# Sheet_2.net
KiCad netlist of a schematic drawn in EasyEDA
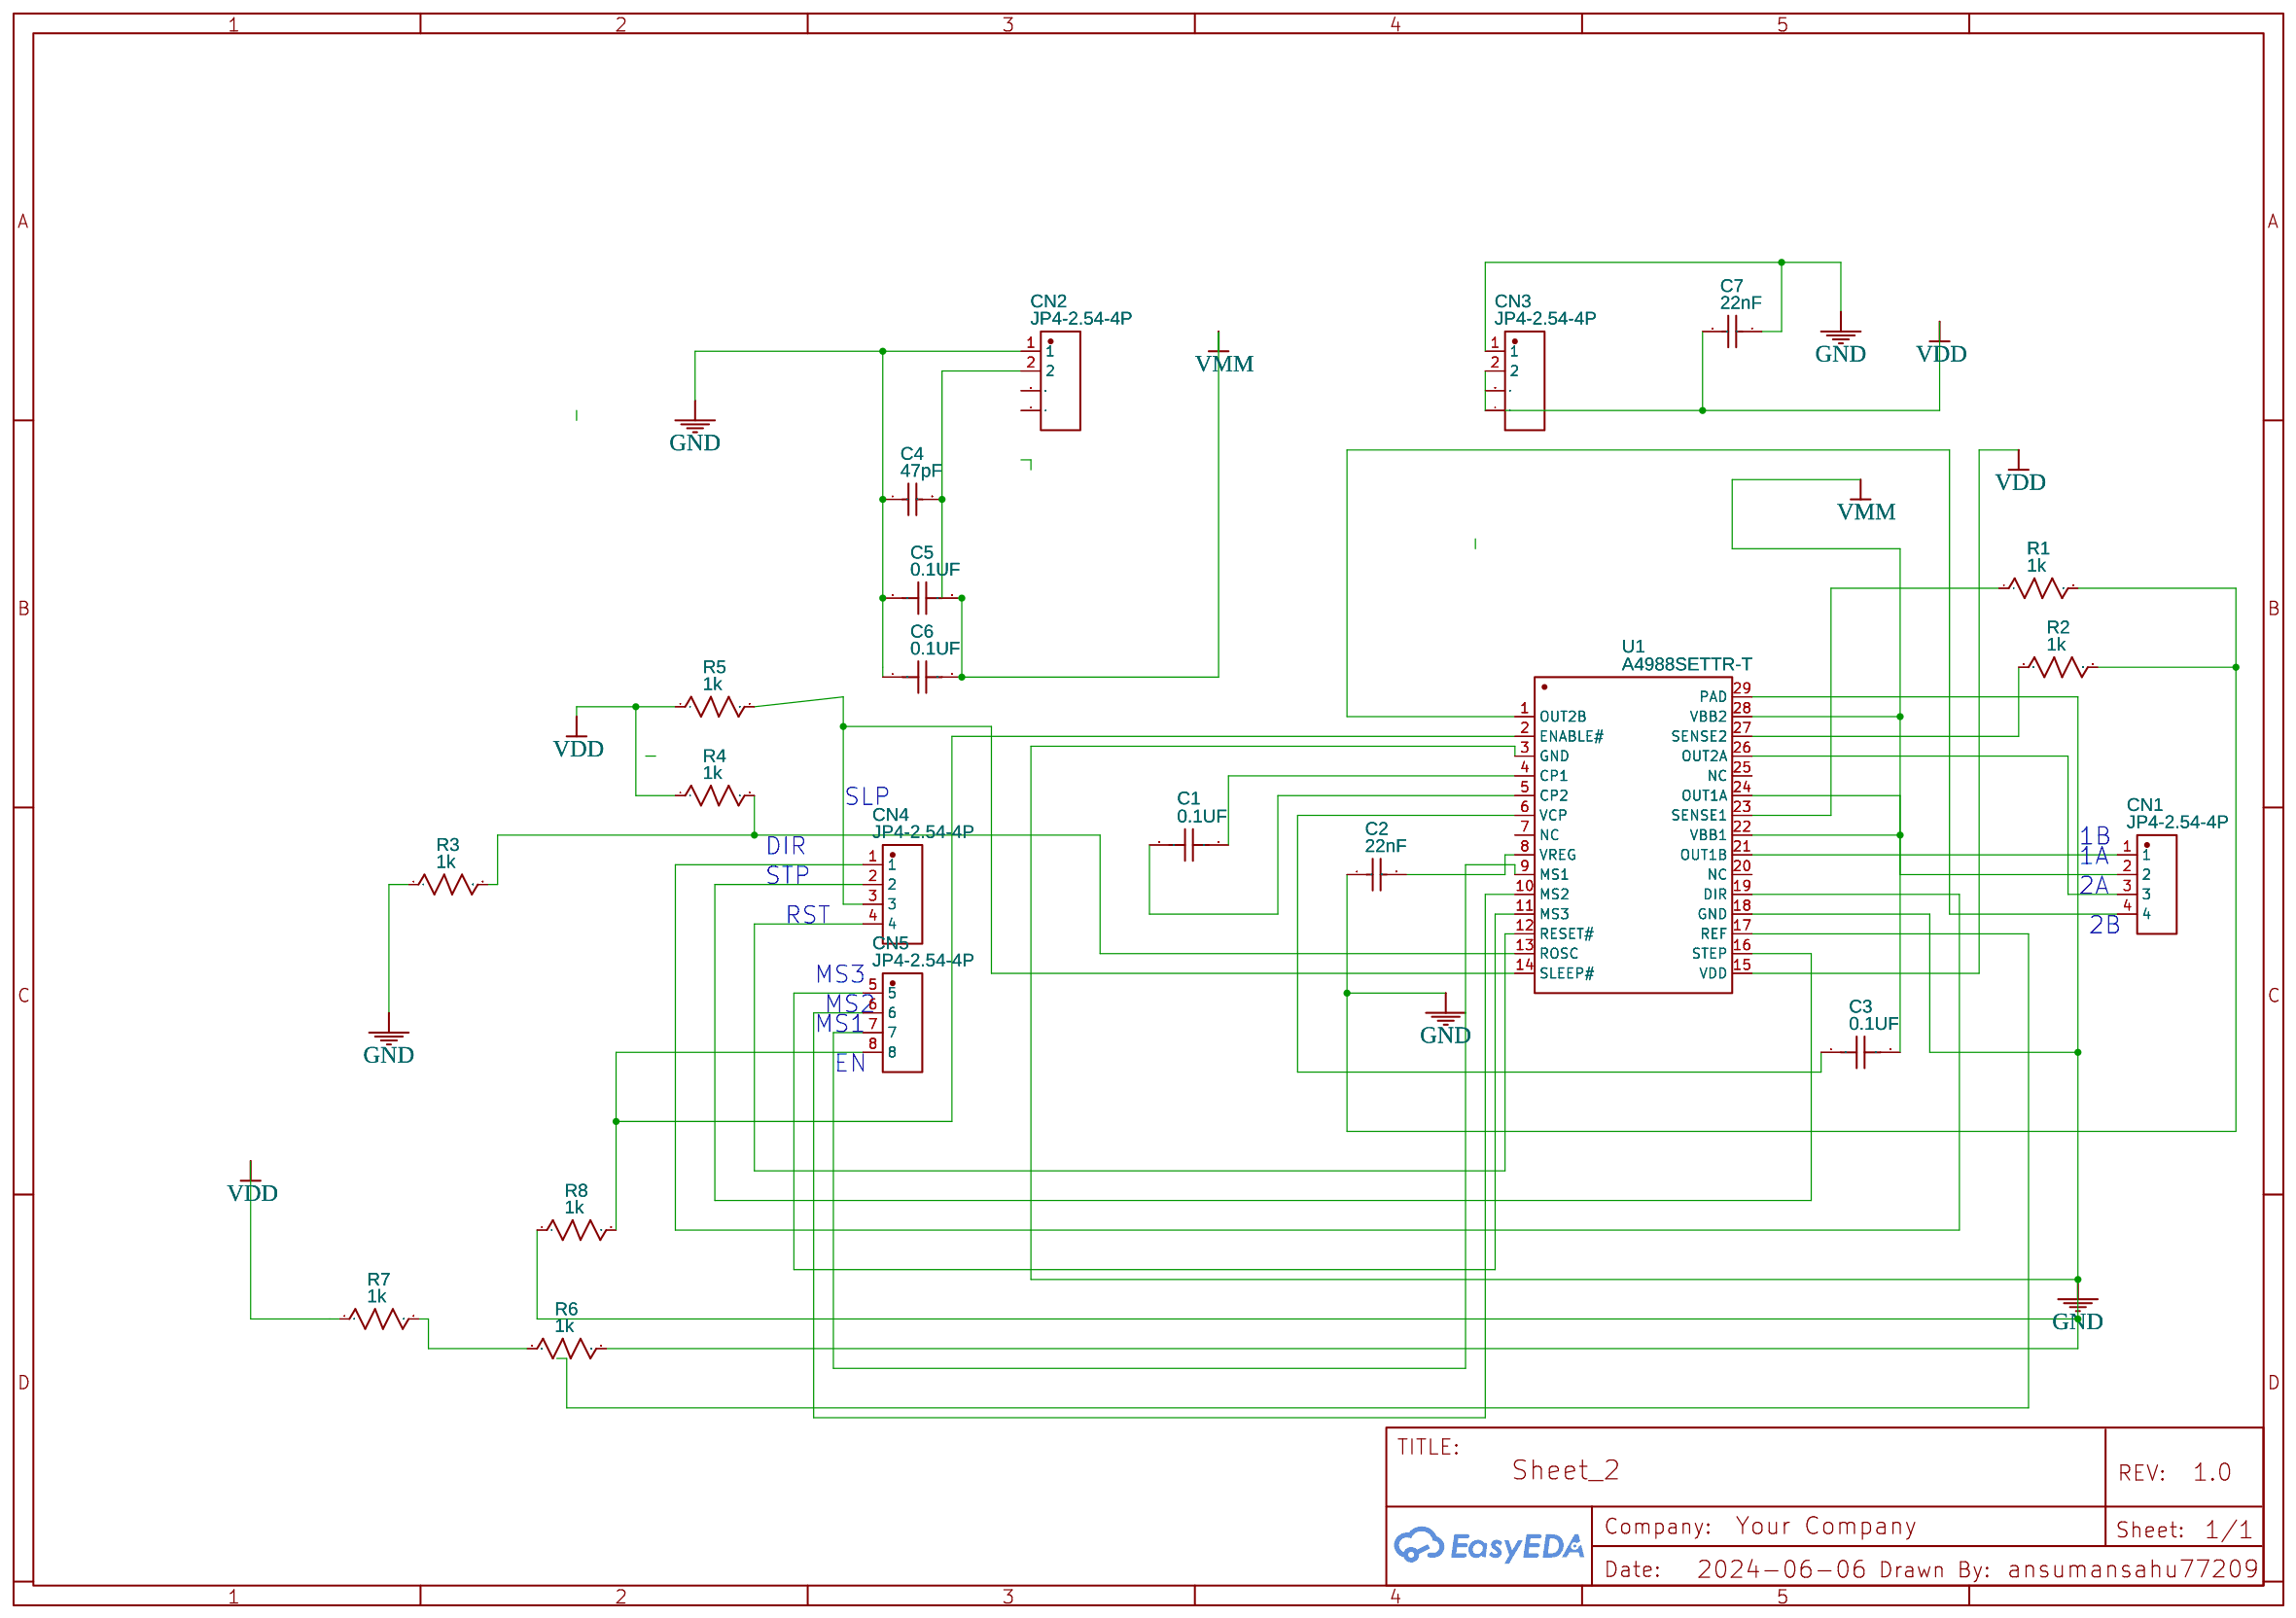
[diagram p0: schematic sheet]

(export (version "E")
  (design (tool "Eeschema 10.0.6"))
  (components
    (comp (ref "C1")
      (value "0.1UF")
      (fields
        (field (name "Manufacturer Part") "250V 0.1UF 5% CBBCapacitor")
        (field (name "Manufacturer") "ReliaPro")
      )
      (libsource (lib "") (part "250V 0.1UF 5% CBBCapacitor"))
    )
    (comp (ref "C2")
      (value "22nF")
      (fields
        (field (name "Manufacturer Part") "Calibration capacitor22NF（223） 100V 5%")
        (field (name "Manufacturer") "ReliaPro")
      )
      (libsource (lib "") (part "Calibration capacitor22NF（223） 100V 5%"))
    )
    (comp (ref "C3")
      (value "0.1UF")
      (fields
        (field (name "Manufacturer Part") "250V 0.1UF 5% CBBCapacitor")
        (field (name "Manufacturer") "ReliaPro")
      )
      (libsource (lib "") (part "250V 0.1UF 5% CBBCapacitor"))
    )
    (comp (ref "C4")
      (value "47pF")
      (fields (field (name "Manufacturer Part") "瓷片电容47PF 3KV"))
      (libsource (lib "") (part "Ceramic capacitors47PF 3KV"))
    )
    (comp (ref "C5")
      (value "0.1UF")
      (fields
        (field (name "Manufacturer Part") "250V 0.1UF 5% CBBCapacitor")
        (field (name "Manufacturer") "ReliaPro")
      )
      (libsource (lib "") (part "250V 0.1UF 5% CBBCapacitor"))
    )
    (comp (ref "C6")
      (value "0.1UF")
      (fields
        (field (name "Manufacturer Part") "250V 0.1UF 5% CBBCapacitor")
        (field (name "Manufacturer") "ReliaPro")
      )
      (libsource (lib "") (part "250V 0.1UF 5% CBBCapacitor"))
    )
    (comp (ref "C7")
      (value "22nF")
      (fields
        (field (name "Manufacturer Part") "Calibration capacitor22NF（223） 100V 5%")
        (field (name "Manufacturer") "ReliaPro")
      )
      (libsource (lib "") (part "Calibration capacitor22NF（223） 100V 5%"))
    )
    (comp (ref "CN1") (value "JP4-2.54-4P") (libsource (lib "") (part "JP4-2.54-4P")))
    (comp (ref "CN2") (value "JP4-2.54-4P") (libsource (lib "") (part "JP4-2.54-4P")))
    (comp (ref "CN3") (value "JP4-2.54-4P") (libsource (lib "") (part "JP4-2.54-4P")))
    (comp (ref "CN4") (value "JP4-2.54-4P") (libsource (lib "") (part "JP4-2.54-4P")))
    (comp (ref "CN5") (value "JP4-2.54-4P") (libsource (lib "") (part "JP4-2.54-4P_1")))
    (comp (ref "R1") (value "1k") (libsource (lib "") (part "R_0603_US")))
    (comp (ref "R2") (value "1k") (libsource (lib "") (part "R_0603_US")))
    (comp (ref "R3") (value "1k") (libsource (lib "") (part "R_0603_US")))
    (comp (ref "R4") (value "1k") (libsource (lib "") (part "R_0603_US")))
    (comp (ref "R5") (value "1k") (libsource (lib "") (part "R_0603_US")))
    (comp (ref "R6") (value "1k") (libsource (lib "") (part "R_0603_US")))
    (comp (ref "R7") (value "1k") (libsource (lib "") (part "R_0603_US")))
    (comp (ref "R8") (value "1k") (libsource (lib "") (part "R_0603_US")))
    (comp (ref "U1")
      (value "A4988SETTR-T")
      (fields (field (name "Manufacturer") "ALLEGRO(美国埃戈罗)"))
      (libsource (lib "") (part "A4988SETTR-T"))
    )
  )
  (nets
    (net (code "1") (name "GND") (class "Default")
      (node (ref "C2") (pin "1") (pinfunction "1_1") (pintype "input"))
      (node (ref "C4") (pin "1") (pinfunction "1_1") (pintype "input"))
      (node (ref "C5") (pin "1") (pinfunction "1_1") (pintype "unspecified"))
      (node (ref "C6") (pin "1") (pinfunction "1_1") (pintype "unspecified"))
      (node (ref "C7") (pin "2") (pinfunction "2_2") (pintype "input"))
      (node (ref "CN2") (pin "1") (pinfunction "1_1") (pintype "unspecified"))
      (node (ref "CN3") (pin "1") (pinfunction "1_1") (pintype "unspecified"))
      (node (ref "R1") (pin "2") (pinfunction "2_2") (pintype "unspecified"))
      (node (ref "R2") (pin "2") (pinfunction "2_2") (pintype "unspecified"))
      (node (ref "R3") (pin "1") (pinfunction "1_1") (pintype "unspecified"))
      (node (ref "R6") (pin "2") (pinfunction "2_2") (pintype "unspecified"))
      (node (ref "R8") (pin "1") (pinfunction "1_1") (pintype "unspecified"))
      (node (ref "U1") (pin "18") (pinfunction "GND_18") (pintype "unspecified"))
      (node (ref "U1") (pin "29") (pinfunction "PAD_29") (pintype "unspecified"))
      (node (ref "U1") (pin "3") (pinfunction "GND_3") (pintype "unspecified"))
    )
    (net (code "2") (name "Net-(R6-Pad1)") (class "Default")
      (node (ref "R6") (pin "1") (pinfunction "1_1") (pintype "unspecified"))
      (node (ref "R7") (pin "2") (pinfunction "2_2") (pintype "unspecified"))
    )
    (net (code "3") (name "Net-(U1-CP1)") (class "Default")
      (node (ref "C1") (pin "2") (pinfunction "2_2") (pintype "unspecified"))
      (node (ref "U1") (pin "4") (pinfunction "CP1_4") (pintype "unspecified"))
    )
    (net (code "4") (name "Net-(U1-CP2)") (class "Default")
      (node (ref "C1") (pin "1") (pinfunction "1_1") (pintype "unspecified"))
      (node (ref "U1") (pin "5") (pinfunction "CP2_5") (pintype "unspecified"))
    )
    (net (code "5") (name "Net-(U1-DIR)") (class "Default")
      (node (ref "CN4") (pin "1") (pinfunction "1_1") (pintype "unspecified"))
      (node (ref "U1") (pin "19") (pinfunction "DIR_19") (pintype "unspecified"))
    )
    (net (code "6") (name "Net-(U1-ENABLE#)") (class "Default")
      (node (ref "CN5") (pin "8") (pinfunction "8_8") (pintype "unspecified"))
      (node (ref "R8") (pin "2") (pinfunction "2_2") (pintype "unspecified"))
      (node (ref "U1") (pin "2") (pinfunction "ENABLE#_2") (pintype "unspecified"))
    )
    (net (code "7") (name "Net-(U1-MS1)") (class "Default")
      (node (ref "CN5") (pin "7") (pinfunction "7_7") (pintype "unspecified"))
      (node (ref "U1") (pin "9") (pinfunction "MS1_9") (pintype "unspecified"))
    )
    (net (code "8") (name "Net-(U1-MS2)") (class "Default")
      (node (ref "CN5") (pin "6") (pinfunction "6_6") (pintype "unspecified"))
      (node (ref "U1") (pin "10") (pinfunction "MS2_10") (pintype "unspecified"))
    )
    (net (code "9") (name "Net-(U1-MS3)") (class "Default")
      (node (ref "CN5") (pin "5") (pinfunction "5_5") (pintype "unspecified"))
      (node (ref "U1") (pin "11") (pinfunction "MS3_11") (pintype "unspecified"))
    )
    (net (code "10") (name "Net-(U1-OUT1B)") (class "Default")
      (node (ref "CN1") (pin "1") (pinfunction "1_1") (pintype "unspecified"))
      (node (ref "U1") (pin "21") (pinfunction "OUT1B_21") (pintype "unspecified"))
    )
    (net (code "11") (name "Net-(U1-OUT2A)") (class "Default")
      (node (ref "CN1") (pin "3") (pinfunction "3_3") (pintype "unspecified"))
      (node (ref "U1") (pin "26") (pinfunction "OUT2A_26") (pintype "unspecified"))
    )
    (net (code "12") (name "Net-(U1-OUT2B)") (class "Default")
      (node (ref "CN1") (pin "4") (pinfunction "4_4") (pintype "unspecified"))
      (node (ref "U1") (pin "1") (pinfunction "OUT2B_1") (pintype "unspecified"))
    )
    (net (code "13") (name "Net-(U1-RESET#)") (class "Default")
      (node (ref "CN4") (pin "4") (pinfunction "4_4") (pintype "unspecified"))
      (node (ref "U1") (pin "12") (pinfunction "RESET#_12") (pintype "unspecified"))
    )
    (net (code "14") (name "Net-(U1-ROSC)") (class "Default")
      (node (ref "R3") (pin "2") (pinfunction "2_2") (pintype "unspecified"))
      (node (ref "R4") (pin "2") (pinfunction "2_2") (pintype "unspecified"))
      (node (ref "U1") (pin "13") (pinfunction "ROSC_13") (pintype "unspecified"))
    )
    (net (code "15") (name "Net-(U1-SENSE1)") (class "Default")
      (node (ref "R1") (pin "1") (pinfunction "1_1") (pintype "unspecified"))
      (node (ref "U1") (pin "23") (pinfunction "SENSE1_23") (pintype "unspecified"))
    )
    (net (code "16") (name "Net-(U1-SENSE2)") (class "Default")
      (node (ref "R2") (pin "1") (pinfunction "1_1") (pintype "unspecified"))
      (node (ref "U1") (pin "27") (pinfunction "SENSE2_27") (pintype "unspecified"))
    )
    (net (code "17") (name "Net-(U1-SLEEP#)") (class "Default")
      (node (ref "CN4") (pin "3") (pinfunction "3_3") (pintype "unspecified"))
      (node (ref "R5") (pin "2") (pinfunction "2_2") (pintype "unspecified"))
      (node (ref "U1") (pin "14") (pinfunction "SLEEP#_14") (pintype "unspecified"))
    )
    (net (code "18") (name "Net-(U1-STEP)") (class "Default")
      (node (ref "CN4") (pin "2") (pinfunction "2_2") (pintype "unspecified"))
      (node (ref "U1") (pin "16") (pinfunction "STEP_16") (pintype "unspecified"))
    )
    (net (code "19") (name "Net-(U1-VCP)") (class "Default")
      (node (ref "C3") (pin "1") (pinfunction "1_1") (pintype "unspecified"))
      (node (ref "U1") (pin "6") (pinfunction "VCP_6") (pintype "unspecified"))
    )
    (net (code "20") (name "Net-(U1-VREG)") (class "Default")
      (node (ref "C2") (pin "2") (pinfunction "2_2") (pintype "input"))
      (node (ref "U1") (pin "8") (pinfunction "VREG_8") (pintype "unspecified"))
    )
    (net (code "21") (name "VDD") (class "Default")
      (node (ref "C7") (pin "1") (pinfunction "1_1") (pintype "input"))
      (node (ref "CN3") (pin "2") (pinfunction "2_2") (pintype "unspecified"))
      (node (ref "CN3") (pin "4") (pinfunction "4_4") (pintype "unspecified"))
      (node (ref "R4") (pin "1") (pinfunction "1_1") (pintype "unspecified"))
      (node (ref "R5") (pin "1") (pinfunction "1_1") (pintype "unspecified"))
      (node (ref "R7") (pin "1") (pinfunction "1_1") (pintype "unspecified"))
      (node (ref "U1") (pin "15") (pinfunction "VDD_15") (pintype "unspecified"))
    )
    (net (code "22") (name "VMM") (class "Default")
      (node (ref "C3") (pin "2") (pinfunction "2_2") (pintype "unspecified"))
      (node (ref "C4") (pin "2") (pinfunction "2_2") (pintype "input"))
      (node (ref "C5") (pin "2") (pinfunction "2_2") (pintype "unspecified"))
      (node (ref "C6") (pin "2") (pinfunction "2_2") (pintype "unspecified"))
      (node (ref "CN1") (pin "2") (pinfunction "2_2") (pintype "unspecified"))
      (node (ref "CN2") (pin "2") (pinfunction "2_2") (pintype "unspecified"))
      (node (ref "U1") (pin "22") (pinfunction "VBB1_22") (pintype "unspecified"))
      (node (ref "U1") (pin "24") (pinfunction "OUT1A_24") (pintype "unspecified"))
      (node (ref "U1") (pin "28") (pinfunction "VBB2_28") (pintype "unspecified"))
    )
    (net (code "23") (name "unconnected-(CN2-Pad3)") (class "Default")
      (node (ref "CN2") (pin "3") (pinfunction "3_3") (pintype "unspecified"))
    )
    (net (code "24") (name "unconnected-(CN2-Pad4)") (class "Default")
      (node (ref "CN2") (pin "4") (pinfunction "4_4") (pintype "unspecified"))
    )
    (net (code "25") (name "unconnected-(CN3-Pad3)") (class "Default")
      (node (ref "CN3") (pin "3") (pinfunction "3_3") (pintype "unspecified"))
    )
    (net (code "26") (name "unconnected-(U1-NC-Pad7)") (class "Default")
      (node (ref "U1") (pin "7") (pinfunction "NC_7") (pintype "unspecified"))
    )
    (net (code "27") (name "unconnected-(U1-NC-Pad20)") (class "Default")
      (node (ref "U1") (pin "20") (pinfunction "NC_20") (pintype "unspecified"))
    )
    (net (code "28") (name "unconnected-(U1-NC-Pad25)") (class "Default")
      (node (ref "U1") (pin "25") (pinfunction "NC_25") (pintype "unspecified"))
    )
    (net (code "29") (name "unconnected-(U1-REF-Pad17)") (class "Default")
      (node (ref "U1") (pin "17") (pinfunction "REF_17") (pintype "unspecified"))
    )
  )
)
